# Sheet1_MB.net
KiCad netlist of a schematic drawn in Altium Designer
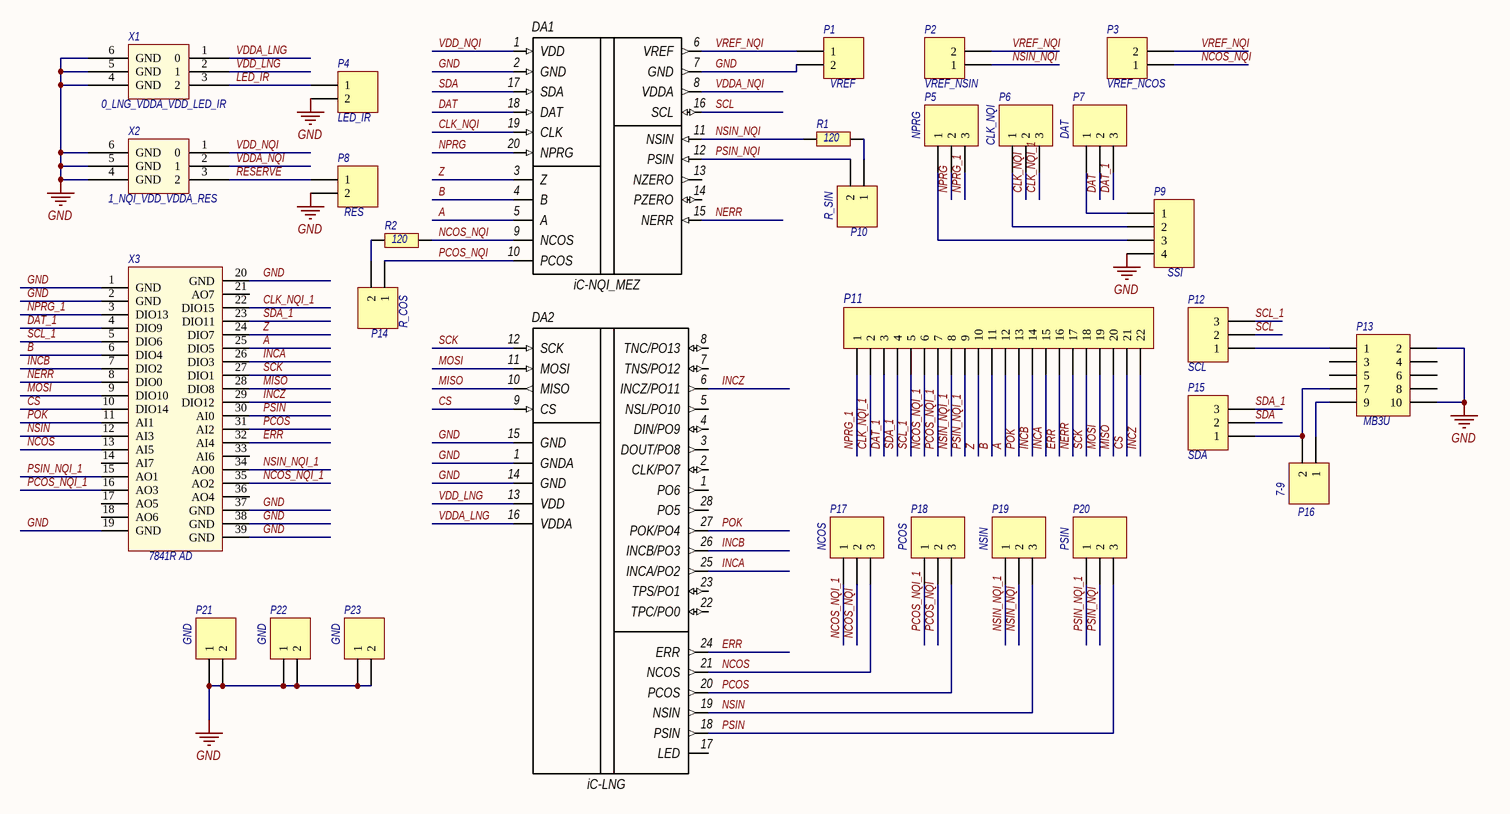
[diagram p0: Sheet1_MB.SchDoc]

(export (version "E")
  (design (tool "Eeschema 10.0.6"))
  (components
    (comp (ref "DA1")
      (value "iC-NQI_MEZ")
      (footprint "iC-NQI_MEZ")
      (description "Оптический энкодер")
      (libsource (lib "VPL") (part "iC-NQI_MEZ"))
    )
    (comp (ref "DA2")
      (value "iC-LNG")
      (footprint "iC_LNG_MEZON")
      (description "Оптический энкодер")
      (libsource (lib "VPL") (part "iC-LNG_MEZ"))
    )
    (comp (ref "P1")
      (value "VREF")
      (footprint "HDR1X2")
      (description "Header, 2-Pin")
      (fields (field (name "PUBLISHER") "Altium Limited"))
      (libsource (lib "") (part "Header 2_3"))
    )
    (comp (ref "P2")
      (value "VREF_NSIN")
      (footprint "HDR1X2")
      (description "Header, 2-Pin")
      (fields (field (name "PUBLISHER") "Altium Limited"))
      (libsource (lib "Miscellaneous Connectors") (part "Header 2"))
    )
    (comp (ref "P3")
      (value "VREF_NCOS")
      (footprint "HDR1X2")
      (description "Header, 2-Pin")
      (fields (field (name "PUBLISHER") "Altium Limited"))
      (libsource (lib "Miscellaneous Connectors") (part "Header 2"))
    )
    (comp (ref "P4")
      (value "LED_IR")
      (footprint "HDR1X2")
      (description "Header, 2-Pin")
      (fields (field (name "PUBLISHER") "Altium Limited"))
      (libsource (lib "") (part "Header 2_3"))
    )
    (comp (ref "P5")
      (value "NPRG")
      (footprint "HDR1X3")
      (description "Header, 3-Pin")
      (fields (field (name "PUBLISHER") "Altium Limited"))
      (libsource (lib "Miscellaneous Connectors") (part "Header 3"))
    )
    (comp (ref "P6")
      (value "CLK_NQI")
      (footprint "HDR1X3")
      (description "Header, 3-Pin")
      (fields (field (name "PUBLISHER") "Altium Limited"))
      (libsource (lib "Miscellaneous Connectors") (part "Header 3"))
    )
    (comp (ref "P7")
      (value "DAT")
      (footprint "HDR1X3")
      (description "Header, 3-Pin")
      (fields (field (name "PUBLISHER") "Altium Limited"))
      (libsource (lib "Miscellaneous Connectors") (part "Header 3"))
    )
    (comp (ref "P8")
      (value "RES")
      (footprint "HDR1X2")
      (description "Header, 2-Pin")
      (fields (field (name "PUBLISHER") "Altium Limited"))
      (libsource (lib "") (part "Header 2_3"))
    )
    (comp (ref "P9")
      (value "SSI")
      (footprint "HDR1X4")
      (description "Header, 4-Pin")
      (fields (field (name "PUBLISHER") "Altium Limited"))
      (libsource (lib "Miscellaneous Connectors") (part "Header 4"))
    )
    (comp (ref "P10")
      (value "R_SIN")
      (footprint "HDR1X2")
      (description "Header, 2-Pin")
      (fields (field (name "PUBLISHER") "Altium Limited"))
      (libsource (lib "") (part "Header 2_2"))
    )
    (comp (ref "P11")
      (value "Header 22")
      (footprint "HDR1X22")
      (description "Header, 22-Pin")
      (fields (field (name "PUBLISHER") "Altium Limited"))
      (libsource (lib "Miscellaneous Connectors") (part "Header 22"))
    )
    (comp (ref "P12")
      (value "SCL")
      (footprint "HDR1X3")
      (description "Header, 3-Pin")
      (fields (field (name "PUBLISHER") "Altium Limited"))
      (libsource (lib "") (part "Header 3_1"))
    )
    (comp (ref "P13")
      (value "MB3U")
      (footprint "HDR2X5")
      (description "Header, 5-Pin, Dual row")
      (fields (field (name "PUBLISHER") "Altium Limited"))
      (libsource (lib "Miscellaneous Connectors") (part "Header 5X2"))
    )
    (comp (ref "P14")
      (value "R_COS")
      (footprint "HDR1X2")
      (description "Header, 2-Pin")
      (fields (field (name "PUBLISHER") "Altium Limited"))
      (libsource (lib "") (part "Header 2_2"))
    )
    (comp (ref "P15")
      (value "SDA")
      (footprint "HDR1X3")
      (description "Header, 3-Pin")
      (fields (field (name "PUBLISHER") "Altium Limited"))
      (libsource (lib "") (part "Header 3_1"))
    )
    (comp (ref "P16")
      (value "7-9")
      (footprint "HDR1X2")
      (description "Header, 2-Pin")
      (fields (field (name "PUBLISHER") "Altium Limited"))
      (libsource (lib "") (part "Header 2_2"))
    )
    (comp (ref "P17")
      (value "NCOS")
      (footprint "HDR1X3")
      (description "Header, 3-Pin")
      (fields (field (name "PUBLISHER") "Altium Limited"))
      (libsource (lib "Miscellaneous Connectors") (part "Header 3"))
    )
    (comp (ref "P18")
      (value "PCOS")
      (footprint "HDR1X3")
      (description "Header, 3-Pin")
      (fields (field (name "PUBLISHER") "Altium Limited"))
      (libsource (lib "Miscellaneous Connectors") (part "Header 3"))
    )
    (comp (ref "P19")
      (value "NSIN")
      (footprint "HDR1X3")
      (description "Header, 3-Pin")
      (fields (field (name "PUBLISHER") "Altium Limited"))
      (libsource (lib "Miscellaneous Connectors") (part "Header 3"))
    )
    (comp (ref "P20")
      (value "PSIN")
      (footprint "HDR1X3")
      (description "Header, 3-Pin")
      (fields (field (name "PUBLISHER") "Altium Limited"))
      (libsource (lib "Miscellaneous Connectors") (part "Header 3"))
    )
    (comp (ref "P21")
      (value "GND")
      (footprint "HDR1X2")
      (description "Header, 2-Pin")
      (fields (field (name "PUBLISHER") "Altium Limited"))
      (libsource (lib "") (part "Header 2_1"))
    )
    (comp (ref "P22")
      (value "GND")
      (footprint "HDR1X2")
      (description "Header, 2-Pin")
      (fields (field (name "PUBLISHER") "Altium Limited"))
      (libsource (lib "") (part "Header 2_1"))
    )
    (comp (ref "P23")
      (value "GND")
      (footprint "HDR1X2")
      (description "Header, 2-Pin")
      (fields (field (name "PUBLISHER") "Altium Limited"))
      (libsource (lib "") (part "Header 2_1"))
    )
    (comp (ref "R1") (value "120") (footprint "RES") (libsource (lib "Schlib") (part "RES")))
    (comp (ref "R2") (value "120") (footprint "RES") (libsource (lib "Schlib") (part "RES")))
    (comp (ref "X1")
      (value "0_LNG_VDDA_VDD_LED_IR")
      (footprint "POWER")
      (libsource (lib "Schlib") (part "POWER"))
    )
    (comp (ref "X2")
      (value "1_NQI_VDD_VDDA_RES")
      (footprint "POWER")
      (libsource (lib "Schlib") (part "POWER"))
    )
    (comp (ref "X3")
      (value "7841R AD")
      (footprint "CHEAP_CONN_FEMALE")
      (libsource (lib "Schlib") (part "CHEAP_CON_37_FEM_7841R_AD"))
    )
  )
  (nets
    (net (code "1") (name "/A") (class "Default")
      (node (ref "DA1") (pin "5") (pinfunction "A_5") (pintype "power_in"))
      (node (ref "P11") (pin "12") (pinfunction "12_12") (pintype "passive"))
      (node (ref "X3") (pin "25") (pinfunction "DIO5_25") (pintype "passive"))
    )
    (net (code "2") (name "/B") (class "Default")
      (node (ref "DA1") (pin "4") (pinfunction "B_4") (pintype "power_in"))
      (node (ref "P11") (pin "11") (pinfunction "11_11") (pintype "passive"))
      (node (ref "X3") (pin "6") (pinfunction "DIO4_6") (pintype "passive"))
    )
    (net (code "3") (name "/CLK_NQI") (class "Default")
      (node (ref "DA1") (pin "19") (pinfunction "CLK_19") (pintype "input"))
      (node (ref "P6") (pin "2") (pinfunction "2_2") (pintype "passive"))
    )
    (net (code "4") (name "/CLK_NQI_1") (class "Default")
      (node (ref "P11") (pin "2") (pinfunction "2_2") (pintype "passive"))
      (node (ref "P6") (pin "3") (pinfunction "3_3") (pintype "passive"))
      (node (ref "X3") (pin "22") (pinfunction "DIO15_22") (pintype "passive"))
    )
    (net (code "5") (name "/CS") (class "Default")
      (node (ref "DA2") (pin "9") (pinfunction "CS_9") (pintype "input"))
      (node (ref "P11") (pin "21") (pinfunction "21_21") (pintype "passive"))
      (node (ref "X3") (pin "10") (pinfunction "DIO14_10") (pintype "passive"))
    )
    (net (code "6") (name "/DAT") (class "Default")
      (node (ref "DA1") (pin "18") (pinfunction "DAT_18") (pintype "input"))
      (node (ref "P7") (pin "2") (pinfunction "2_2") (pintype "passive"))
    )
    (net (code "7") (name "/DAT_1") (class "Default")
      (node (ref "P11") (pin "3") (pinfunction "3_3") (pintype "passive"))
      (node (ref "P7") (pin "3") (pinfunction "3_3") (pintype "passive"))
      (node (ref "X3") (pin "4") (pinfunction "DIO9_4") (pintype "passive"))
    )
    (net (code "8") (name "/ERR") (class "Default")
      (node (ref "DA2") (pin "24") (pinfunction "ERR_24") (pintype "output"))
      (node (ref "P11") (pin "16") (pinfunction "16_16") (pintype "passive"))
      (node (ref "X3") (pin "32") (pinfunction "AI4_32") (pintype "passive"))
    )
    (net (code "9") (name "/INCA") (class "Default")
      (node (ref "DA2") (pin "25") (pinfunction "INCA/PO2_25") (pintype "output"))
      (node (ref "P11") (pin "15") (pinfunction "15_15") (pintype "passive"))
      (node (ref "X3") (pin "26") (pinfunction "DIO3_26") (pintype "passive"))
    )
    (net (code "10") (name "/INCB") (class "Default")
      (node (ref "DA2") (pin "26") (pinfunction "INCB/PO3_26") (pintype "output"))
      (node (ref "P11") (pin "14") (pinfunction "14_14") (pintype "passive"))
      (node (ref "X3") (pin "7") (pinfunction "DIO2_7") (pintype "passive"))
    )
    (net (code "11") (name "/INCZ") (class "Default")
      (node (ref "DA2") (pin "6") (pinfunction "INCZ/PO11_6") (pintype "output"))
      (node (ref "P11") (pin "22") (pinfunction "22_22") (pintype "passive"))
      (node (ref "X3") (pin "29") (pinfunction "DIO12_29") (pintype "passive"))
    )
    (net (code "12") (name "/LED_IR") (class "Default")
      (node (ref "P4") (pin "1") (pinfunction "1_1") (pintype "passive"))
      (node (ref "X1") (pin "3") (pinfunction "2_3") (pintype "passive"))
    )
    (net (code "13") (name "/MISO") (class "Default")
      (node (ref "DA2") (pin "10") (pinfunction "MISO_10") (pintype "output"))
      (node (ref "P11") (pin "20") (pinfunction "20_20") (pintype "passive"))
      (node (ref "X3") (pin "28") (pinfunction "DIO8_28") (pintype "passive"))
    )
    (net (code "14") (name "/MOSI") (class "Default")
      (node (ref "DA2") (pin "11") (pinfunction "MOSI_11") (pintype "input"))
      (node (ref "P11") (pin "19") (pinfunction "19_19") (pintype "passive"))
      (node (ref "X3") (pin "9") (pinfunction "DIO10_9") (pintype "passive"))
    )
    (net (code "15") (name "/NCOS") (class "Default")
      (node (ref "DA2") (pin "21") (pinfunction "NCOS_21") (pintype "output"))
      (node (ref "P17") (pin "3") (pinfunction "3_3") (pintype "passive"))
      (node (ref "X3") (pin "13") (pinfunction "AI5_13") (pintype "passive"))
    )
    (net (code "16") (name "/NCOS_NQI") (class "Default")
      (node (ref "DA1") (pin "9") (pinfunction "NCOS_9") (pintype "power_in"))
      (node (ref "P17") (pin "2") (pinfunction "2_2") (pintype "passive"))
      (node (ref "P3") (pin "1") (pinfunction "1_1") (pintype "passive"))
      (node (ref "R2") (pin "1") (pinfunction "1_1") (pintype "passive"))
    )
    (net (code "17") (name "/NCOS_NQI_1") (class "Default")
      (node (ref "P11") (pin "6") (pinfunction "6_6") (pintype "passive"))
      (node (ref "P17") (pin "1") (pinfunction "1_1") (pintype "passive"))
      (node (ref "X3") (pin "35") (pinfunction "AO2_35") (pintype "passive"))
    )
    (net (code "18") (name "/NERR") (class "Default")
      (node (ref "DA1") (pin "15") (pinfunction "NERR_15") (pintype "input"))
      (node (ref "P11") (pin "17") (pinfunction "17_17") (pintype "passive"))
      (node (ref "X3") (pin "8") (pinfunction "DIO0_8") (pintype "passive"))
    )
    (net (code "19") (name "/NPRG") (class "Default")
      (node (ref "DA1") (pin "20") (pinfunction "NPRG_20") (pintype "input"))
      (node (ref "P5") (pin "2") (pinfunction "2_2") (pintype "passive"))
    )
    (net (code "20") (name "/NPRG_1") (class "Default")
      (node (ref "P11") (pin "1") (pinfunction "1_1") (pintype "passive"))
      (node (ref "P5") (pin "3") (pinfunction "3_3") (pintype "passive"))
      (node (ref "X3") (pin "3") (pinfunction "DIO13_3") (pintype "passive"))
    )
    (net (code "21") (name "/NSIN") (class "Default")
      (node (ref "DA2") (pin "19") (pinfunction "NSIN_19") (pintype "output"))
      (node (ref "P19") (pin "3") (pinfunction "3_3") (pintype "passive"))
      (node (ref "X3") (pin "12") (pinfunction "AI3_12") (pintype "passive"))
    )
    (net (code "22") (name "/NSIN_NQI") (class "Default")
      (node (ref "DA1") (pin "11") (pinfunction "NSIN_11") (pintype "input"))
      (node (ref "P19") (pin "2") (pinfunction "2_2") (pintype "passive"))
      (node (ref "P2") (pin "1") (pinfunction "1_1") (pintype "passive"))
      (node (ref "R1") (pin "2") (pinfunction "2_2") (pintype "passive"))
    )
    (net (code "23") (name "/NSIN_NQI_1") (class "Default")
      (node (ref "P11") (pin "8") (pinfunction "8_8") (pintype "passive"))
      (node (ref "P19") (pin "1") (pinfunction "1_1") (pintype "passive"))
      (node (ref "X3") (pin "34") (pinfunction "AO0_34") (pintype "passive"))
    )
    (net (code "24") (name "/PCOS") (class "Default")
      (node (ref "DA2") (pin "20") (pinfunction "PCOS_20") (pintype "output"))
      (node (ref "P18") (pin "3") (pinfunction "3_3") (pintype "passive"))
      (node (ref "X3") (pin "31") (pinfunction "AI2_31") (pintype "passive"))
    )
    (net (code "25") (name "/PCOS_NQI") (class "Default")
      (node (ref "DA1") (pin "10") (pinfunction "PCOS_10") (pintype "power_in"))
      (node (ref "P14") (pin "1") (pinfunction "1_1") (pintype "passive"))
      (node (ref "P18") (pin "2") (pinfunction "2_2") (pintype "passive"))
    )
    (net (code "26") (name "/PCOS_NQI_1") (class "Default")
      (node (ref "P11") (pin "7") (pinfunction "7_7") (pintype "passive"))
      (node (ref "P18") (pin "1") (pinfunction "1_1") (pintype "passive"))
      (node (ref "X3") (pin "16") (pinfunction "AO3_16") (pintype "passive"))
    )
    (net (code "27") (name "/POK") (class "Default")
      (node (ref "DA2") (pin "27") (pinfunction "POK/PO4_27") (pintype "output"))
      (node (ref "P11") (pin "13") (pinfunction "13_13") (pintype "passive"))
      (node (ref "X3") (pin "11") (pinfunction "AI1_11") (pintype "passive"))
    )
    (net (code "28") (name "/PSIN") (class "Default")
      (node (ref "DA2") (pin "18") (pinfunction "PSIN_18") (pintype "output"))
      (node (ref "P20") (pin "3") (pinfunction "3_3") (pintype "passive"))
      (node (ref "X3") (pin "30") (pinfunction "AI0_30") (pintype "passive"))
    )
    (net (code "29") (name "/PSIN_NQI") (class "Default")
      (node (ref "DA1") (pin "12") (pinfunction "PSIN_12") (pintype "input"))
      (node (ref "P10") (pin "2") (pinfunction "2_2") (pintype "passive"))
      (node (ref "P20") (pin "2") (pinfunction "2_2") (pintype "passive"))
    )
    (net (code "30") (name "/PSIN_NQI_1") (class "Default")
      (node (ref "P11") (pin "9") (pinfunction "9_9") (pintype "passive"))
      (node (ref "P20") (pin "1") (pinfunction "1_1") (pintype "passive"))
      (node (ref "X3") (pin "15") (pinfunction "AO1_15") (pintype "passive"))
    )
    (net (code "31") (name "/RESERVE") (class "Default")
      (node (ref "P8") (pin "1") (pinfunction "1_1") (pintype "passive"))
      (node (ref "X2") (pin "3") (pinfunction "2_3") (pintype "passive"))
    )
    (net (code "32") (name "/SCK") (class "Default")
      (node (ref "DA2") (pin "12") (pinfunction "SCK_12") (pintype "input"))
      (node (ref "P11") (pin "18") (pinfunction "18_18") (pintype "passive"))
      (node (ref "X3") (pin "27") (pinfunction "DIO1_27") (pintype "passive"))
    )
    (net (code "33") (name "/SCL") (class "Default")
      (node (ref "DA1") (pin "16") (pinfunction "SCL_16") (pintype "bidirectional"))
      (node (ref "P12") (pin "2") (pinfunction "2_2") (pintype "passive"))
    )
    (net (code "34") (name "/SCL_1") (class "Default")
      (node (ref "P11") (pin "5") (pinfunction "5_5") (pintype "passive"))
      (node (ref "P12") (pin "3") (pinfunction "3_3") (pintype "passive"))
      (node (ref "X3") (pin "5") (pinfunction "DIO6_5") (pintype "passive"))
    )
    (net (code "35") (name "/SDA") (class "Default")
      (node (ref "DA1") (pin "17") (pinfunction "SDA_17") (pintype "input"))
      (node (ref "P15") (pin "2") (pinfunction "2_2") (pintype "passive"))
    )
    (net (code "36") (name "/SDA_1") (class "Default")
      (node (ref "P11") (pin "4") (pinfunction "4_4") (pintype "passive"))
      (node (ref "P15") (pin "3") (pinfunction "3_3") (pintype "passive"))
      (node (ref "X3") (pin "23") (pinfunction "DIO11_23") (pintype "passive"))
    )
    (net (code "37") (name "/VDDA_LNG") (class "Default")
      (node (ref "DA2") (pin "16") (pinfunction "VDDA_16") (pintype "power_in"))
      (node (ref "X1") (pin "1") (pinfunction "0_1") (pintype "passive"))
    )
    (net (code "38") (name "/VDDA_NQI") (class "Default")
      (node (ref "DA1") (pin "8") (pinfunction "VDDA_8") (pintype "output"))
      (node (ref "X2") (pin "2") (pinfunction "1_2") (pintype "passive"))
    )
    (net (code "39") (name "/VDD_LNG") (class "Default")
      (node (ref "DA2") (pin "13") (pinfunction "VDD_13") (pintype "power_in"))
      (node (ref "X1") (pin "2") (pinfunction "1_2") (pintype "passive"))
    )
    (net (code "40") (name "/VDD_NQI") (class "Default")
      (node (ref "DA1") (pin "1") (pinfunction "VDD_1") (pintype "input"))
      (node (ref "X2") (pin "1") (pinfunction "0_1") (pintype "passive"))
    )
    (net (code "41") (name "/VREF_NQI") (class "Default")
      (node (ref "DA1") (pin "6") (pinfunction "VREF_6") (pintype "output"))
      (node (ref "P1") (pin "1") (pinfunction "1_1") (pintype "passive"))
      (node (ref "P2") (pin "2") (pinfunction "2_2") (pintype "passive"))
      (node (ref "P3") (pin "2") (pinfunction "2_2") (pintype "passive"))
    )
    (net (code "42") (name "/Z") (class "Default")
      (node (ref "DA1") (pin "3") (pinfunction "Z_3") (pintype "power_in"))
      (node (ref "P11") (pin "10") (pinfunction "10_10") (pintype "passive"))
      (node (ref "X3") (pin "24") (pinfunction "DIO7_24") (pintype "passive"))
    )
    (net (code "43") (name "GND") (class "Default")
      (node (ref "DA1") (pin "2") (pinfunction "GND_2") (pintype "input"))
      (node (ref "DA1") (pin "7") (pinfunction "GND_7") (pintype "output"))
      (node (ref "DA2") (pin "1") (pinfunction "GNDA_1") (pintype "power_in"))
      (node (ref "DA2") (pin "14") (pinfunction "GND_14") (pintype "power_in"))
      (node (ref "DA2") (pin "15") (pinfunction "GND_15") (pintype "passive"))
      (node (ref "P1") (pin "2") (pinfunction "2_2") (pintype "passive"))
      (node (ref "P13") (pin "10") (pinfunction "10_10") (pintype "passive"))
      (node (ref "P13") (pin "2") (pinfunction "2_2") (pintype "passive"))
      (node (ref "P21") (pin "1") (pinfunction "1_1") (pintype "passive"))
      (node (ref "P21") (pin "2") (pinfunction "2_2") (pintype "passive"))
      (node (ref "P22") (pin "1") (pinfunction "1_1") (pintype "passive"))
      (node (ref "P22") (pin "2") (pinfunction "2_2") (pintype "passive"))
      (node (ref "P23") (pin "1") (pinfunction "1_1") (pintype "passive"))
      (node (ref "P23") (pin "2") (pinfunction "2_2") (pintype "passive"))
      (node (ref "P4") (pin "2") (pinfunction "2_2") (pintype "passive"))
      (node (ref "P8") (pin "2") (pinfunction "2_2") (pintype "passive"))
      (node (ref "P9") (pin "4") (pinfunction "4_4") (pintype "passive"))
      (node (ref "X1") (pin "4") (pinfunction "GND_4") (pintype "passive"))
      (node (ref "X1") (pin "5") (pinfunction "GND_5") (pintype "passive"))
      (node (ref "X1") (pin "6") (pinfunction "GND_6") (pintype "passive"))
      (node (ref "X2") (pin "4") (pinfunction "GND_4") (pintype "passive"))
      (node (ref "X2") (pin "5") (pinfunction "GND_5") (pintype "passive"))
      (node (ref "X2") (pin "6") (pinfunction "GND_6") (pintype "passive"))
      (node (ref "X3") (pin "1") (pinfunction "GND_1") (pintype "passive"))
      (node (ref "X3") (pin "19") (pinfunction "GND_19") (pintype "passive"))
      (node (ref "X3") (pin "2") (pinfunction "GND_2") (pintype "passive"))
      (node (ref "X3") (pin "20") (pinfunction "GND_20") (pintype "passive"))
      (node (ref "X3") (pin "37") (pinfunction "GND_37") (pintype "passive"))
      (node (ref "X3") (pin "38") (pinfunction "GND_38") (pintype "passive"))
      (node (ref "X3") (pin "39") (pinfunction "GND_39") (pintype "passive"))
    )
    (net (code "44") (name "Net-(P5-Pad1)") (class "Default")
      (node (ref "P5") (pin "1") (pinfunction "1_1") (pintype "passive"))
      (node (ref "P9") (pin "3") (pinfunction "3_3") (pintype "passive"))
    )
    (net (code "45") (name "Net-(P6-Pad1)") (class "Default")
      (node (ref "P6") (pin "1") (pinfunction "1_1") (pintype "passive"))
      (node (ref "P9") (pin "2") (pinfunction "2_2") (pintype "passive"))
    )
    (net (code "46") (name "Net-(P7-Pad1)") (class "Default")
      (node (ref "P7") (pin "1") (pinfunction "1_1") (pintype "passive"))
      (node (ref "P9") (pin "1") (pinfunction "1_1") (pintype "passive"))
    )
    (net (code "47") (name "Net-(P10-Pad1)") (class "Default")
      (node (ref "P10") (pin "1") (pinfunction "1_1") (pintype "passive"))
      (node (ref "R1") (pin "1") (pinfunction "1_1") (pintype "passive"))
    )
    (net (code "48") (name "Net-(P12-Pad1)") (class "Default")
      (node (ref "P12") (pin "1") (pinfunction "1_1") (pintype "passive"))
      (node (ref "P13") (pin "1") (pinfunction "1_1") (pintype "passive"))
    )
    (net (code "49") (name "Net-(P13-Pad7)") (class "Default")
      (node (ref "P13") (pin "7") (pinfunction "7_7") (pintype "passive"))
      (node (ref "P15") (pin "1") (pinfunction "1_1") (pintype "passive"))
      (node (ref "P16") (pin "2") (pinfunction "2_2") (pintype "passive"))
    )
    (net (code "50") (name "Net-(P13-Pad9)") (class "Default")
      (node (ref "P13") (pin "9") (pinfunction "9_9") (pintype "passive"))
      (node (ref "P16") (pin "1") (pinfunction "1_1") (pintype "passive"))
    )
    (net (code "51") (name "Net-(P14-Pad2)") (class "Default")
      (node (ref "P14") (pin "2") (pinfunction "2_2") (pintype "passive"))
      (node (ref "R2") (pin "2") (pinfunction "2_2") (pintype "passive"))
    )
    (net (code "52") (name "unconnected-(DA1-NZERO-Pad13)") (class "Default")
      (node (ref "DA1") (pin "13") (pinfunction "NZERO_13") (pintype "output"))
    )
    (net (code "53") (name "unconnected-(DA1-PZERO-Pad14)") (class "Default")
      (node (ref "DA1") (pin "14") (pinfunction "PZERO_14") (pintype "bidirectional"))
    )
    (net (code "54") (name "unconnected-(DA2-CLK{slash}PO7-Pad2)") (class "Default")
      (node (ref "DA2") (pin "2") (pinfunction "CLK/PO7_2") (pintype "bidirectional"))
    )
    (net (code "55") (name "unconnected-(DA2-DIN{slash}PO9-Pad4)") (class "Default")
      (node (ref "DA2") (pin "4") (pinfunction "DIN/PO9_4") (pintype "bidirectional"))
    )
    (net (code "56") (name "unconnected-(DA2-DOUT{slash}PO8-Pad3)") (class "Default")
      (node (ref "DA2") (pin "3") (pinfunction "DOUT/PO8_3") (pintype "output"))
    )
    (net (code "57") (name "unconnected-(DA2-LED-Pad17)") (class "Default")
      (node (ref "DA2") (pin "17") (pinfunction "LED_17") (pintype "power_in"))
    )
    (net (code "58") (name "unconnected-(DA2-NSL{slash}PO10-Pad5)") (class "Default")
      (node (ref "DA2") (pin "5") (pinfunction "NSL/PO10_5") (pintype "output"))
    )
    (net (code "59") (name "unconnected-(DA2-PO5-Pad28)") (class "Default")
      (node (ref "DA2") (pin "28") (pinfunction "PO5_28") (pintype "output"))
    )
    (net (code "60") (name "unconnected-(DA2-PO6-Pad1)") (class "Default")
      (node (ref "DA2") (pin "1") (pinfunction "PO6_1") (pintype "output"))
    )
    (net (code "61") (name "unconnected-(DA2-TNC{slash}PO13-Pad8)") (class "Default")
      (node (ref "DA2") (pin "8") (pinfunction "TNC/PO13_8") (pintype "bidirectional"))
    )
    (net (code "62") (name "unconnected-(DA2-TNS{slash}PO12-Pad7)") (class "Default")
      (node (ref "DA2") (pin "7") (pinfunction "TNS/PO12_7") (pintype "bidirectional"))
    )
    (net (code "63") (name "unconnected-(DA2-TPC{slash}PO0-Pad22)") (class "Default")
      (node (ref "DA2") (pin "22") (pinfunction "TPC/PO0_22") (pintype "bidirectional"))
    )
    (net (code "64") (name "unconnected-(DA2-TPS{slash}PO1-Pad23)") (class "Default")
      (node (ref "DA2") (pin "23") (pinfunction "TPS/PO1_23") (pintype "bidirectional"))
    )
    (net (code "65") (name "unconnected-(P13-Pad3)") (class "Default")
      (node (ref "P13") (pin "3") (pinfunction "3_3") (pintype "passive"))
    )
    (net (code "66") (name "unconnected-(P13-Pad4)") (class "Default")
      (node (ref "P13") (pin "4") (pinfunction "4_4") (pintype "passive"))
    )
    (net (code "67") (name "unconnected-(P13-Pad5)") (class "Default")
      (node (ref "P13") (pin "5") (pinfunction "5_5") (pintype "passive"))
    )
    (net (code "68") (name "unconnected-(P13-Pad6)") (class "Default")
      (node (ref "P13") (pin "6") (pinfunction "6_6") (pintype "passive"))
    )
    (net (code "69") (name "unconnected-(P13-Pad8)") (class "Default")
      (node (ref "P13") (pin "8") (pinfunction "8_8") (pintype "passive"))
    )
    (net (code "70") (name "unconnected-(X3-AI6-Pad33)") (class "Default")
      (node (ref "X3") (pin "33") (pinfunction "AI6_33") (pintype "passive"))
    )
    (net (code "71") (name "unconnected-(X3-AI7-Pad14)") (class "Default")
      (node (ref "X3") (pin "14") (pinfunction "AI7_14") (pintype "passive"))
    )
    (net (code "72") (name "unconnected-(X3-AO4-Pad36)") (class "Default")
      (node (ref "X3") (pin "36") (pinfunction "AO4_36") (pintype "passive"))
    )
    (net (code "73") (name "unconnected-(X3-AO5-Pad17)") (class "Default")
      (node (ref "X3") (pin "17") (pinfunction "AO5_17") (pintype "passive"))
    )
    (net (code "74") (name "unconnected-(X3-AO6-Pad18)") (class "Default")
      (node (ref "X3") (pin "18") (pinfunction "AO6_18") (pintype "passive"))
    )
    (net (code "75") (name "unconnected-(X3-AO7-Pad21)") (class "Default")
      (node (ref "X3") (pin "21") (pinfunction "AO7_21") (pintype "passive"))
    )
  )
)
